# DriverV2_0.net
KiCad netlist of a schematic drawn in Altium Designer
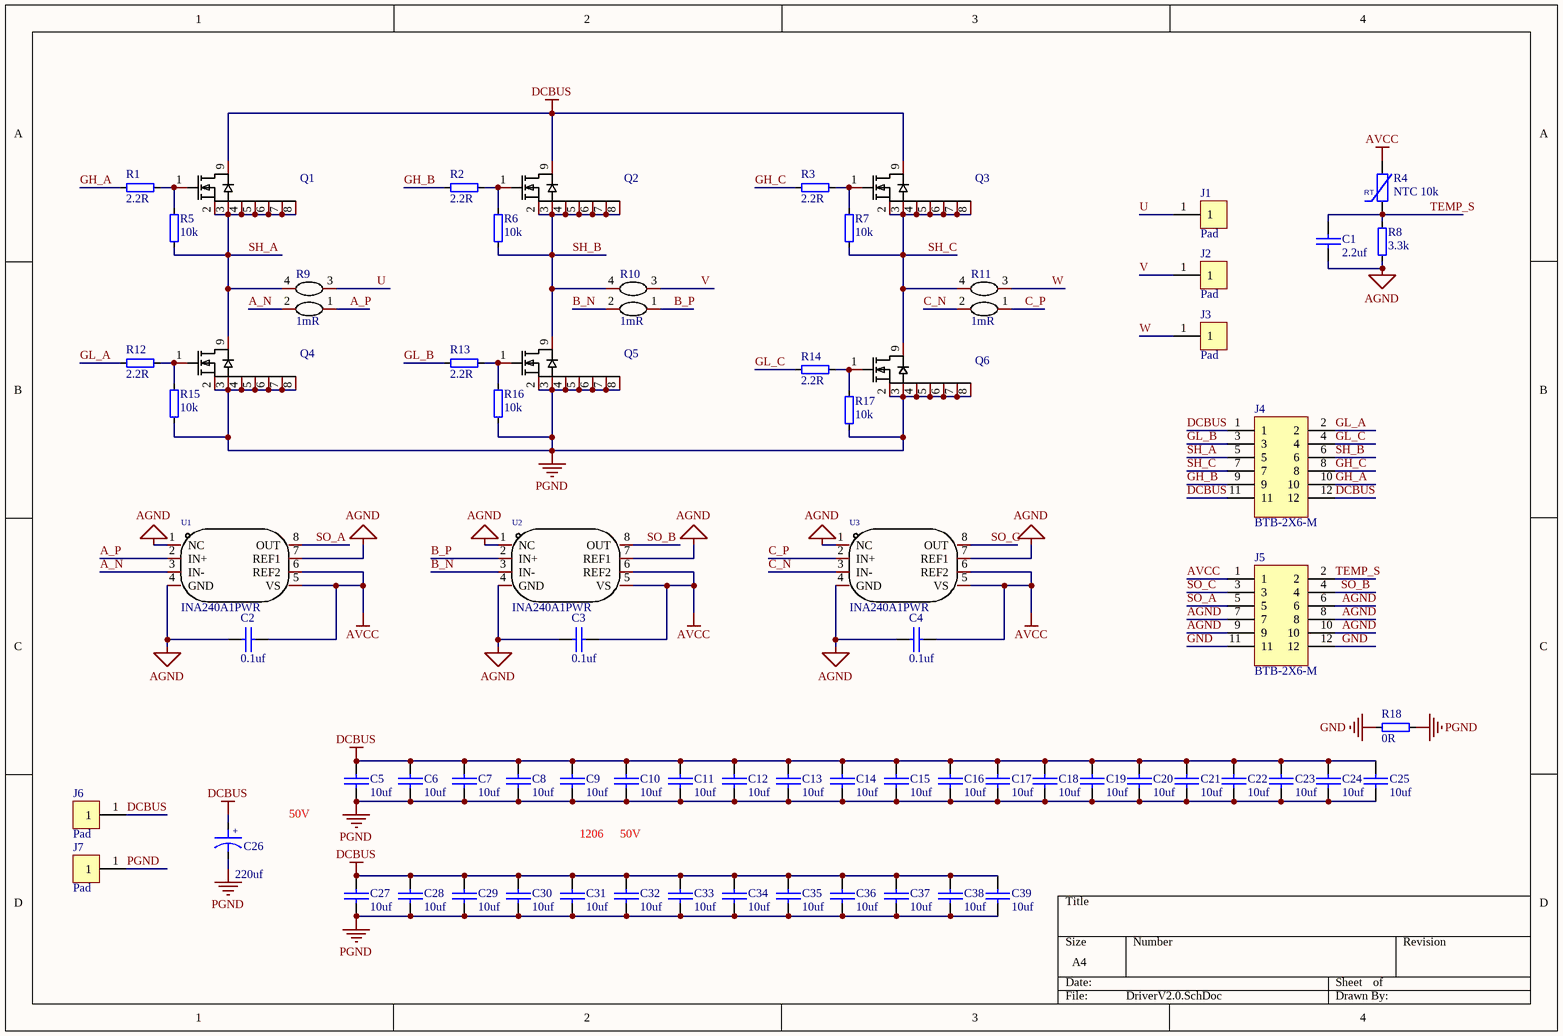
[diagram p0: DriverV2.0.SchDoc]

(export (version "E")
  (design (tool "Eeschema 10.0.6"))
  (components
    (comp (ref "C1")
      (value "2.2uf")
      (footprint "0603C")
      (description "贴片电容")
      (libsource (lib "Driver") (part "CAP"))
    )
    (comp (ref "C2")
      (value "0.1uf")
      (footprint "0603C")
      (description "贴片电容")
      (libsource (lib "Driver") (part "CAP"))
    )
    (comp (ref "C3")
      (value "0.1uf")
      (footprint "0603C")
      (description "贴片电容")
      (libsource (lib "Driver") (part "CAP"))
    )
    (comp (ref "C4")
      (value "0.1uf")
      (footprint "0603C")
      (description "贴片电容")
      (libsource (lib "Driver") (part "CAP"))
    )
    (comp (ref "C5")
      (value "10uf")
      (footprint "1206C")
      (description "贴片电容")
      (libsource (lib "Driver") (part "CAP"))
    )
    (comp (ref "C6")
      (value "10uf")
      (footprint "1206C")
      (description "贴片电容")
      (libsource (lib "Driver") (part "CAP"))
    )
    (comp (ref "C7")
      (value "10uf")
      (footprint "1206C")
      (description "贴片电容")
      (libsource (lib "Driver") (part "CAP"))
    )
    (comp (ref "C8")
      (value "10uf")
      (footprint "1206C")
      (description "贴片电容")
      (libsource (lib "Driver") (part "CAP"))
    )
    (comp (ref "C9")
      (value "10uf")
      (footprint "1206C")
      (description "贴片电容")
      (libsource (lib "Driver") (part "CAP"))
    )
    (comp (ref "C10")
      (value "10uf")
      (footprint "1206C")
      (description "贴片电容")
      (libsource (lib "Driver") (part "CAP"))
    )
    (comp (ref "C11")
      (value "10uf")
      (footprint "1206C")
      (description "贴片电容")
      (libsource (lib "Driver") (part "CAP"))
    )
    (comp (ref "C12")
      (value "10uf")
      (footprint "1206C")
      (description "贴片电容")
      (libsource (lib "Driver") (part "CAP"))
    )
    (comp (ref "C13")
      (value "10uf")
      (footprint "1206C")
      (description "贴片电容")
      (libsource (lib "Driver") (part "CAP"))
    )
    (comp (ref "C14")
      (value "10uf")
      (footprint "1206C")
      (description "贴片电容")
      (libsource (lib "Driver") (part "CAP"))
    )
    (comp (ref "C15")
      (value "10uf")
      (footprint "1206C")
      (description "贴片电容")
      (libsource (lib "Driver") (part "CAP"))
    )
    (comp (ref "C16")
      (value "10uf")
      (footprint "1206C")
      (description "贴片电容")
      (libsource (lib "Driver") (part "CAP"))
    )
    (comp (ref "C17")
      (value "10uf")
      (footprint "1206C")
      (description "贴片电容")
      (libsource (lib "Driver") (part "CAP"))
    )
    (comp (ref "C18")
      (value "10uf")
      (footprint "1206C")
      (description "贴片电容")
      (libsource (lib "Driver") (part "CAP"))
    )
    (comp (ref "C19")
      (value "10uf")
      (footprint "1206C")
      (description "贴片电容")
      (libsource (lib "Driver") (part "CAP"))
    )
    (comp (ref "C20")
      (value "10uf")
      (footprint "1206C")
      (description "贴片电容")
      (libsource (lib "Driver") (part "CAP"))
    )
    (comp (ref "C21")
      (value "10uf")
      (footprint "1206C")
      (description "贴片电容")
      (libsource (lib "Driver") (part "CAP"))
    )
    (comp (ref "C22")
      (value "10uf")
      (footprint "1206C")
      (description "贴片电容")
      (libsource (lib "Driver") (part "CAP"))
    )
    (comp (ref "C23")
      (value "10uf")
      (footprint "1206C")
      (description "贴片电容")
      (libsource (lib "Driver") (part "CAP"))
    )
    (comp (ref "C24")
      (value "10uf")
      (footprint "1206C")
      (description "贴片电容")
      (libsource (lib "Driver") (part "CAP"))
    )
    (comp (ref "C25")
      (value "10uf")
      (footprint "1206C")
      (description "贴片电容")
      (libsource (lib "Driver") (part "CAP"))
    )
    (comp (ref "C26")
      (value "220uf")
      (footprint "ELECTRO10-5-N")
      (description "极性电容")
      (libsource (lib "Driver") (part "CAP+"))
    )
    (comp (ref "C27")
      (value "10uf")
      (footprint "1206C")
      (description "贴片电容")
      (libsource (lib "Driver") (part "CAP"))
    )
    (comp (ref "C28")
      (value "10uf")
      (footprint "1206C")
      (description "贴片电容")
      (libsource (lib "Driver") (part "CAP"))
    )
    (comp (ref "C29")
      (value "10uf")
      (footprint "1206C")
      (description "贴片电容")
      (libsource (lib "Driver") (part "CAP"))
    )
    (comp (ref "C30")
      (value "10uf")
      (footprint "1206C")
      (description "贴片电容")
      (libsource (lib "Driver") (part "CAP"))
    )
    (comp (ref "C31")
      (value "10uf")
      (footprint "1206C")
      (description "贴片电容")
      (libsource (lib "Driver") (part "CAP"))
    )
    (comp (ref "C32")
      (value "10uf")
      (footprint "1206C")
      (description "贴片电容")
      (libsource (lib "Driver") (part "CAP"))
    )
    (comp (ref "C33")
      (value "10uf")
      (footprint "1206C")
      (description "贴片电容")
      (libsource (lib "Driver") (part "CAP"))
    )
    (comp (ref "C34")
      (value "10uf")
      (footprint "1206C")
      (description "贴片电容")
      (libsource (lib "Driver") (part "CAP"))
    )
    (comp (ref "C35")
      (value "10uf")
      (footprint "1206C")
      (description "贴片电容")
      (libsource (lib "Driver") (part "CAP"))
    )
    (comp (ref "C36")
      (value "10uf")
      (footprint "1206C")
      (description "贴片电容")
      (libsource (lib "Driver") (part "CAP"))
    )
    (comp (ref "C37")
      (value "10uf")
      (footprint "1206C")
      (description "贴片电容")
      (libsource (lib "Driver") (part "CAP"))
    )
    (comp (ref "C38")
      (value "10uf")
      (footprint "1206C")
      (description "贴片电容")
      (libsource (lib "Driver") (part "CAP"))
    )
    (comp (ref "C39")
      (value "10uf")
      (footprint "1206C")
      (description "贴片电容")
      (libsource (lib "Driver") (part "CAP"))
    )
    (comp (ref "J1")
      (value "Pad")
      (footprint "PAD")
      (description "焊盘")
      (libsource (lib "Driver") (part "Pad"))
    )
    (comp (ref "J2")
      (value "Pad")
      (footprint "PAD")
      (description "焊盘")
      (libsource (lib "Driver") (part "Pad"))
    )
    (comp (ref "J3")
      (value "Pad")
      (footprint "PAD")
      (description "焊盘")
      (libsource (lib "Driver") (part "Pad"))
    )
    (comp (ref "J4")
      (value "BTB-2X6-M")
      (footprint "BTB-M-0.8mm-2x6P")
      (description "0.8间距2x6P公座")
      (libsource (lib "Driver") (part "BTB-2X6-M"))
    )
    (comp (ref "J5")
      (value "BTB-2X6-M")
      (footprint "BTB-M-0.8mm-2x6P")
      (description "0.8间距2x6P公座")
      (libsource (lib "Driver") (part "BTB-2X6-M"))
    )
    (comp (ref "J6") (value "Pad") (footprint "PAD") (description "焊盘") (libsource (lib "") (part "Pad_1")))
    (comp (ref "J7") (value "Pad") (footprint "PAD") (description "焊盘") (libsource (lib "") (part "Pad_1")))
    (comp (ref "Q1")
      (value "HYG006N04LS1TA")
      (footprint "TOLL")
      (description "N沟道增强型MOS 40V-600A")
      (fields (field (name "MANUFACTURER") "HUAYI(华羿微)"))
      (libsource (lib "Driver") (part "HYG006N04LS1TA"))
    )
    (comp (ref "Q2")
      (value "HYG006N04LS1TA")
      (footprint "TOLL")
      (description "N沟道增强型MOS 40V-600A")
      (fields (field (name "MANUFACTURER") "HUAYI(华羿微)"))
      (libsource (lib "Driver") (part "HYG006N04LS1TA"))
    )
    (comp (ref "Q3")
      (value "HYG006N04LS1TA")
      (footprint "TOLL")
      (description "N沟道增强型MOS 40V-600A")
      (fields (field (name "MANUFACTURER") "HUAYI(华羿微)"))
      (libsource (lib "Driver") (part "HYG006N04LS1TA"))
    )
    (comp (ref "Q4")
      (value "HYG006N04LS1TA")
      (footprint "TOLL")
      (description "N沟道增强型MOS 40V-600A")
      (fields (field (name "MANUFACTURER") "HUAYI(华羿微)"))
      (libsource (lib "Driver") (part "HYG006N04LS1TA"))
    )
    (comp (ref "Q5")
      (value "HYG006N04LS1TA")
      (footprint "TOLL")
      (description "N沟道增强型MOS 40V-600A")
      (fields (field (name "MANUFACTURER") "HUAYI(华羿微)"))
      (libsource (lib "Driver") (part "HYG006N04LS1TA"))
    )
    (comp (ref "Q6")
      (value "HYG006N04LS1TA")
      (footprint "TOLL")
      (description "N沟道增强型MOS 40V-600A")
      (fields (field (name "MANUFACTURER") "HUAYI(华羿微)"))
      (libsource (lib "Driver") (part "HYG006N04LS1TA"))
    )
    (comp (ref "R1")
      (value "2.2R")
      (footprint "0603R")
      (description "贴片电阻")
      (libsource (lib "Driver") (part "RES"))
    )
    (comp (ref "R2")
      (value "2.2R")
      (footprint "0603R")
      (description "贴片电阻")
      (libsource (lib "Driver") (part "RES"))
    )
    (comp (ref "R3")
      (value "2.2R")
      (footprint "0603R")
      (description "贴片电阻")
      (libsource (lib "Driver") (part "RES"))
    )
    (comp (ref "R4")
      (value "NTC 10k")
      (footprint "0805R")
      (description "热敏电阻")
      (libsource (lib "Driver") (part "RT"))
    )
    (comp (ref "R5")
      (value "10k")
      (footprint "0603R")
      (description "贴片电阻")
      (libsource (lib "Driver") (part "RES"))
    )
    (comp (ref "R6")
      (value "10k")
      (footprint "0603R")
      (description "贴片电阻")
      (libsource (lib "Driver") (part "RES"))
    )
    (comp (ref "R7")
      (value "10k")
      (footprint "0603R")
      (description "贴片电阻")
      (libsource (lib "Driver") (part "RES"))
    )
    (comp (ref "R8")
      (value "3.3k")
      (footprint "0603R")
      (description "贴片电阻")
      (libsource (lib "Driver") (part "RES"))
    )
    (comp (ref "R9")
      (value "1mR")
      (footprint "3637R")
      (description "四脚采样电阻")
      (fields
        (field (name "MANUFACTURER") "Milliohm(毫欧)")
        (field (name "MANUFACTURER PART") "HoLR3637-5-R010-F")
      )
      (libsource (lib "Driver") (part "HoLR3637"))
    )
    (comp (ref "R10")
      (value "1mR")
      (footprint "3637R")
      (description "四脚采样电阻")
      (fields
        (field (name "MANUFACTURER") "Milliohm(毫欧)")
        (field (name "MANUFACTURER PART") "HoLR3637-5-R010-F")
      )
      (libsource (lib "Driver") (part "HoLR3637"))
    )
    (comp (ref "R11")
      (value "1mR")
      (footprint "3637R")
      (description "四脚采样电阻")
      (fields
        (field (name "MANUFACTURER") "Milliohm(毫欧)")
        (field (name "MANUFACTURER PART") "HoLR3637-5-R010-F")
      )
      (libsource (lib "Driver") (part "HoLR3637"))
    )
    (comp (ref "R12")
      (value "2.2R")
      (footprint "0603R")
      (description "贴片电阻")
      (libsource (lib "Driver") (part "RES"))
    )
    (comp (ref "R13")
      (value "2.2R")
      (footprint "0603R")
      (description "贴片电阻")
      (libsource (lib "Driver") (part "RES"))
    )
    (comp (ref "R14")
      (value "2.2R")
      (footprint "0603R")
      (description "贴片电阻")
      (libsource (lib "Driver") (part "RES"))
    )
    (comp (ref "R15")
      (value "10k")
      (footprint "0603R")
      (description "贴片电阻")
      (libsource (lib "Driver") (part "RES"))
    )
    (comp (ref "R16")
      (value "10k")
      (footprint "0603R")
      (description "贴片电阻")
      (libsource (lib "Driver") (part "RES"))
    )
    (comp (ref "R17")
      (value "10k")
      (footprint "0603R")
      (description "贴片电阻")
      (libsource (lib "Driver") (part "RES"))
    )
    (comp (ref "R18")
      (value "0R")
      (footprint "0603R")
      (description "贴片电阻")
      (libsource (lib "Driver") (part "RES"))
    )
    (comp (ref "U1")
      (value "INA240A1PWR")
      (footprint "TSSOP-8")
      (fields (field (name "MANUFACTURER") "TI(德州仪器)") (field (name "NAME") "INA240A1PWR"))
      (libsource (lib "Driver") (part "INA240A1PWR"))
    )
    (comp (ref "U2")
      (value "INA240A1PWR")
      (footprint "TSSOP-8")
      (fields (field (name "MANUFACTURER") "TI(德州仪器)") (field (name "NAME") "INA240A1PWR"))
      (libsource (lib "Driver") (part "INA240A1PWR"))
    )
    (comp (ref "U3")
      (value "INA240A1PWR")
      (footprint "TSSOP-8")
      (fields (field (name "MANUFACTURER") "TI(德州仪器)") (field (name "NAME") "INA240A1PWR"))
      (libsource (lib "Driver") (part "INA240A1PWR"))
    )
  )
  (nets
    (net (code "1") (name "/A_N") (class "Default")
      (node (ref "R9") (pin "2") (pinfunction "2_2") (pintype "passive"))
      (node (ref "U1") (pin "3") (pinfunction "IN-_3") (pintype "passive"))
    )
    (net (code "2") (name "/A_P") (class "Default")
      (node (ref "R9") (pin "1") (pinfunction "1_1") (pintype "passive"))
      (node (ref "U1") (pin "2") (pinfunction "IN+_2") (pintype "passive"))
    )
    (net (code "3") (name "/B_N") (class "Default")
      (node (ref "R10") (pin "2") (pinfunction "2_2") (pintype "passive"))
      (node (ref "U2") (pin "3") (pinfunction "IN-_3") (pintype "passive"))
    )
    (net (code "4") (name "/B_P") (class "Default")
      (node (ref "R10") (pin "1") (pinfunction "1_1") (pintype "passive"))
      (node (ref "U2") (pin "2") (pinfunction "IN+_2") (pintype "passive"))
    )
    (net (code "5") (name "/C_N") (class "Default")
      (node (ref "R11") (pin "2") (pinfunction "2_2") (pintype "passive"))
      (node (ref "U3") (pin "3") (pinfunction "IN-_3") (pintype "passive"))
    )
    (net (code "6") (name "/C_P") (class "Default")
      (node (ref "R11") (pin "1") (pinfunction "1_1") (pintype "passive"))
      (node (ref "U3") (pin "2") (pinfunction "IN+_2") (pintype "passive"))
    )
    (net (code "7") (name "/GH_A") (class "Default")
      (node (ref "J4") (pin "10") (pinfunction "10_10") (pintype "passive"))
      (node (ref "R1") (pin "1") (pinfunction "1_1") (pintype "passive"))
    )
    (net (code "8") (name "/GH_B") (class "Default")
      (node (ref "J4") (pin "9") (pinfunction "9_9") (pintype "passive"))
      (node (ref "R2") (pin "1") (pinfunction "1_1") (pintype "passive"))
    )
    (net (code "9") (name "/GH_C") (class "Default")
      (node (ref "J4") (pin "8") (pinfunction "8_8") (pintype "passive"))
      (node (ref "R3") (pin "1") (pinfunction "1_1") (pintype "passive"))
    )
    (net (code "10") (name "/GL_A") (class "Default")
      (node (ref "J4") (pin "2") (pinfunction "2_2") (pintype "passive"))
      (node (ref "R12") (pin "1") (pinfunction "1_1") (pintype "passive"))
    )
    (net (code "11") (name "/GL_B") (class "Default")
      (node (ref "J4") (pin "3") (pinfunction "3_3") (pintype "passive"))
      (node (ref "R13") (pin "1") (pinfunction "1_1") (pintype "passive"))
    )
    (net (code "12") (name "/GL_C") (class "Default")
      (node (ref "J4") (pin "4") (pinfunction "4_4") (pintype "passive"))
      (node (ref "R14") (pin "1") (pinfunction "1_1") (pintype "passive"))
    )
    (net (code "13") (name "/SH_A") (class "Default")
      (node (ref "J4") (pin "5") (pinfunction "5_5") (pintype "passive"))
      (node (ref "Q1") (pin "2") (pinfunction "S_2") (pintype "passive"))
      (node (ref "Q1") (pin "3") (pinfunction "S_3") (pintype "passive"))
      (node (ref "Q1") (pin "4") (pinfunction "S_4") (pintype "passive"))
      (node (ref "Q1") (pin "5") (pinfunction "S_5") (pintype "passive"))
      (node (ref "Q1") (pin "6") (pinfunction "S_6") (pintype "passive"))
      (node (ref "Q1") (pin "7") (pinfunction "S_7") (pintype "passive"))
      (node (ref "Q1") (pin "8") (pinfunction "S_8") (pintype "passive"))
      (node (ref "Q4") (pin "9") (pinfunction "D_9") (pintype "passive"))
      (node (ref "R5") (pin "1") (pinfunction "1_1") (pintype "passive"))
      (node (ref "R9") (pin "4") (pinfunction "4_4") (pintype "passive"))
    )
    (net (code "14") (name "/SH_B") (class "Default")
      (node (ref "J4") (pin "6") (pinfunction "6_6") (pintype "passive"))
      (node (ref "Q2") (pin "2") (pinfunction "S_2") (pintype "passive"))
      (node (ref "Q2") (pin "3") (pinfunction "S_3") (pintype "passive"))
      (node (ref "Q2") (pin "4") (pinfunction "S_4") (pintype "passive"))
      (node (ref "Q2") (pin "5") (pinfunction "S_5") (pintype "passive"))
      (node (ref "Q2") (pin "6") (pinfunction "S_6") (pintype "passive"))
      (node (ref "Q2") (pin "7") (pinfunction "S_7") (pintype "passive"))
      (node (ref "Q2") (pin "8") (pinfunction "S_8") (pintype "passive"))
      (node (ref "Q5") (pin "9") (pinfunction "D_9") (pintype "passive"))
      (node (ref "R10") (pin "4") (pinfunction "4_4") (pintype "passive"))
      (node (ref "R6") (pin "1") (pinfunction "1_1") (pintype "passive"))
    )
    (net (code "15") (name "/SH_C") (class "Default")
      (node (ref "J4") (pin "7") (pinfunction "7_7") (pintype "passive"))
      (node (ref "Q3") (pin "2") (pinfunction "S_2") (pintype "passive"))
      (node (ref "Q3") (pin "3") (pinfunction "S_3") (pintype "passive"))
      (node (ref "Q3") (pin "4") (pinfunction "S_4") (pintype "passive"))
      (node (ref "Q3") (pin "5") (pinfunction "S_5") (pintype "passive"))
      (node (ref "Q3") (pin "6") (pinfunction "S_6") (pintype "passive"))
      (node (ref "Q3") (pin "7") (pinfunction "S_7") (pintype "passive"))
      (node (ref "Q3") (pin "8") (pinfunction "S_8") (pintype "passive"))
      (node (ref "Q6") (pin "9") (pinfunction "D_9") (pintype "passive"))
      (node (ref "R11") (pin "4") (pinfunction "4_4") (pintype "passive"))
      (node (ref "R7") (pin "1") (pinfunction "1_1") (pintype "passive"))
    )
    (net (code "16") (name "/SO_A") (class "Default")
      (node (ref "J5") (pin "5") (pinfunction "5_5") (pintype "passive"))
      (node (ref "U1") (pin "8") (pinfunction "OUT_8") (pintype "passive"))
    )
    (net (code "17") (name "/SO_B") (class "Default")
      (node (ref "J5") (pin "4") (pinfunction "4_4") (pintype "passive"))
      (node (ref "U2") (pin "8") (pinfunction "OUT_8") (pintype "passive"))
    )
    (net (code "18") (name "/SO_C") (class "Default")
      (node (ref "J5") (pin "3") (pinfunction "3_3") (pintype "passive"))
      (node (ref "U3") (pin "8") (pinfunction "OUT_8") (pintype "passive"))
    )
    (net (code "19") (name "/TEMP_S") (class "Default")
      (node (ref "C1") (pin "1") (pinfunction "1_1") (pintype "passive"))
      (node (ref "J5") (pin "2") (pinfunction "2_2") (pintype "passive"))
      (node (ref "R4") (pin "1") (pinfunction "1_1") (pintype "passive"))
      (node (ref "R8") (pin "2") (pinfunction "2_2") (pintype "passive"))
    )
    (net (code "20") (name "/U") (class "Default")
      (node (ref "J1") (pin "1") (pinfunction "1_1") (pintype "passive"))
      (node (ref "R9") (pin "3") (pinfunction "3_3") (pintype "passive"))
    )
    (net (code "21") (name "/V") (class "Default")
      (node (ref "J2") (pin "1") (pinfunction "1_1") (pintype "passive"))
      (node (ref "R10") (pin "3") (pinfunction "3_3") (pintype "passive"))
    )
    (net (code "22") (name "/W") (class "Default")
      (node (ref "J3") (pin "1") (pinfunction "1_1") (pintype "passive"))
      (node (ref "R11") (pin "3") (pinfunction "3_3") (pintype "passive"))
    )
    (net (code "23") (name "AGND") (class "Default")
      (node (ref "C1") (pin "2") (pinfunction "2_2") (pintype "passive"))
      (node (ref "C2") (pin "1") (pinfunction "1_1") (pintype "passive"))
      (node (ref "C3") (pin "1") (pinfunction "1_1") (pintype "passive"))
      (node (ref "C4") (pin "1") (pinfunction "1_1") (pintype "passive"))
      (node (ref "J5") (pin "10") (pinfunction "10_10") (pintype "passive"))
      (node (ref "J5") (pin "6") (pinfunction "6_6") (pintype "passive"))
      (node (ref "J5") (pin "7") (pinfunction "7_7") (pintype "passive"))
      (node (ref "J5") (pin "8") (pinfunction "8_8") (pintype "passive"))
      (node (ref "J5") (pin "9") (pinfunction "9_9") (pintype "passive"))
      (node (ref "R8") (pin "1") (pinfunction "1_1") (pintype "passive"))
      (node (ref "U1") (pin "1") (pinfunction "NC_1") (pintype "passive"))
      (node (ref "U1") (pin "4") (pinfunction "GND_4") (pintype "passive"))
      (node (ref "U1") (pin "7") (pinfunction "REF1_7") (pintype "passive"))
      (node (ref "U2") (pin "1") (pinfunction "NC_1") (pintype "passive"))
      (node (ref "U2") (pin "4") (pinfunction "GND_4") (pintype "passive"))
      (node (ref "U2") (pin "7") (pinfunction "REF1_7") (pintype "passive"))
      (node (ref "U3") (pin "1") (pinfunction "NC_1") (pintype "passive"))
      (node (ref "U3") (pin "4") (pinfunction "GND_4") (pintype "passive"))
      (node (ref "U3") (pin "7") (pinfunction "REF1_7") (pintype "passive"))
    )
    (net (code "24") (name "AVCC") (class "Default")
      (node (ref "C2") (pin "2") (pinfunction "2_2") (pintype "passive"))
      (node (ref "C3") (pin "2") (pinfunction "2_2") (pintype "passive"))
      (node (ref "C4") (pin "2") (pinfunction "2_2") (pintype "passive"))
      (node (ref "J5") (pin "1") (pinfunction "1_1") (pintype "passive"))
      (node (ref "R4") (pin "2") (pinfunction "2_2") (pintype "passive"))
      (node (ref "U1") (pin "5") (pinfunction "VS_5") (pintype "passive"))
      (node (ref "U1") (pin "6") (pinfunction "REF2_6") (pintype "passive"))
      (node (ref "U2") (pin "5") (pinfunction "VS_5") (pintype "passive"))
      (node (ref "U2") (pin "6") (pinfunction "REF2_6") (pintype "passive"))
      (node (ref "U3") (pin "5") (pinfunction "VS_5") (pintype "passive"))
      (node (ref "U3") (pin "6") (pinfunction "REF2_6") (pintype "passive"))
    )
    (net (code "25") (name "DCBUS") (class "Default")
      (node (ref "C10") (pin "1") (pinfunction "1_1") (pintype "passive"))
      (node (ref "C11") (pin "1") (pinfunction "1_1") (pintype "passive"))
      (node (ref "C12") (pin "1") (pinfunction "1_1") (pintype "passive"))
      (node (ref "C13") (pin "1") (pinfunction "1_1") (pintype "passive"))
      (node (ref "C14") (pin "1") (pinfunction "1_1") (pintype "passive"))
      (node (ref "C15") (pin "1") (pinfunction "1_1") (pintype "passive"))
      (node (ref "C16") (pin "1") (pinfunction "1_1") (pintype "passive"))
      (node (ref "C17") (pin "1") (pinfunction "1_1") (pintype "passive"))
      (node (ref "C18") (pin "1") (pinfunction "1_1") (pintype "passive"))
      (node (ref "C19") (pin "1") (pinfunction "1_1") (pintype "passive"))
      (node (ref "C20") (pin "1") (pinfunction "1_1") (pintype "passive"))
      (node (ref "C21") (pin "1") (pinfunction "1_1") (pintype "passive"))
      (node (ref "C22") (pin "1") (pinfunction "1_1") (pintype "passive"))
      (node (ref "C23") (pin "1") (pinfunction "1_1") (pintype "passive"))
      (node (ref "C24") (pin "1") (pinfunction "1_1") (pintype "passive"))
      (node (ref "C25") (pin "1") (pinfunction "1_1") (pintype "passive"))
      (node (ref "C26") (pin "1") (pinfunction "1_1") (pintype "passive"))
      (node (ref "C27") (pin "1") (pinfunction "1_1") (pintype "passive"))
      (node (ref "C28") (pin "1") (pinfunction "1_1") (pintype "passive"))
      (node (ref "C29") (pin "1") (pinfunction "1_1") (pintype "passive"))
      (node (ref "C30") (pin "1") (pinfunction "1_1") (pintype "passive"))
      (node (ref "C31") (pin "1") (pinfunction "1_1") (pintype "passive"))
      (node (ref "C32") (pin "1") (pinfunction "1_1") (pintype "passive"))
      (node (ref "C33") (pin "1") (pinfunction "1_1") (pintype "passive"))
      (node (ref "C34") (pin "1") (pinfunction "1_1") (pintype "passive"))
      (node (ref "C35") (pin "1") (pinfunction "1_1") (pintype "passive"))
      (node (ref "C36") (pin "1") (pinfunction "1_1") (pintype "passive"))
      (node (ref "C37") (pin "1") (pinfunction "1_1") (pintype "passive"))
      (node (ref "C38") (pin "1") (pinfunction "1_1") (pintype "passive"))
      (node (ref "C39") (pin "1") (pinfunction "1_1") (pintype "passive"))
      (node (ref "C5") (pin "1") (pinfunction "1_1") (pintype "passive"))
      (node (ref "C6") (pin "1") (pinfunction "1_1") (pintype "passive"))
      (node (ref "C7") (pin "1") (pinfunction "1_1") (pintype "passive"))
      (node (ref "C8") (pin "1") (pinfunction "1_1") (pintype "passive"))
      (node (ref "C9") (pin "1") (pinfunction "1_1") (pintype "passive"))
      (node (ref "J4") (pin "1") (pinfunction "1_1") (pintype "passive"))
      (node (ref "J4") (pin "11") (pinfunction "11_11") (pintype "passive"))
      (node (ref "J4") (pin "12") (pinfunction "12_12") (pintype "passive"))
      (node (ref "J6") (pin "1") (pinfunction "1_1") (pintype "passive"))
      (node (ref "Q1") (pin "9") (pinfunction "D_9") (pintype "passive"))
      (node (ref "Q2") (pin "9") (pinfunction "D_9") (pintype "passive"))
      (node (ref "Q3") (pin "9") (pinfunction "D_9") (pintype "passive"))
    )
    (net (code "26") (name "GND") (class "Default")
      (node (ref "J5") (pin "11") (pinfunction "11_11") (pintype "passive"))
      (node (ref "J5") (pin "12") (pinfunction "12_12") (pintype "passive"))
      (node (ref "R18") (pin "2") (pinfunction "2_2") (pintype "passive"))
    )
    (net (code "27") (name "Net-(Q1-G)") (class "Default")
      (node (ref "Q1") (pin "1") (pinfunction "G_1") (pintype "passive"))
      (node (ref "R1") (pin "2") (pinfunction "2_2") (pintype "passive"))
      (node (ref "R5") (pin "2") (pinfunction "2_2") (pintype "passive"))
    )
    (net (code "28") (name "Net-(Q2-G)") (class "Default")
      (node (ref "Q2") (pin "1") (pinfunction "G_1") (pintype "passive"))
      (node (ref "R2") (pin "2") (pinfunction "2_2") (pintype "passive"))
      (node (ref "R6") (pin "2") (pinfunction "2_2") (pintype "passive"))
    )
    (net (code "29") (name "Net-(Q3-G)") (class "Default")
      (node (ref "Q3") (pin "1") (pinfunction "G_1") (pintype "passive"))
      (node (ref "R3") (pin "2") (pinfunction "2_2") (pintype "passive"))
      (node (ref "R7") (pin "2") (pinfunction "2_2") (pintype "passive"))
    )
    (net (code "30") (name "Net-(Q4-G)") (class "Default")
      (node (ref "Q4") (pin "1") (pinfunction "G_1") (pintype "passive"))
      (node (ref "R12") (pin "2") (pinfunction "2_2") (pintype "passive"))
      (node (ref "R15") (pin "2") (pinfunction "2_2") (pintype "passive"))
    )
    (net (code "31") (name "Net-(Q5-G)") (class "Default")
      (node (ref "Q5") (pin "1") (pinfunction "G_1") (pintype "passive"))
      (node (ref "R13") (pin "2") (pinfunction "2_2") (pintype "passive"))
      (node (ref "R16") (pin "2") (pinfunction "2_2") (pintype "passive"))
    )
    (net (code "32") (name "Net-(Q6-G)") (class "Default")
      (node (ref "Q6") (pin "1") (pinfunction "G_1") (pintype "passive"))
      (node (ref "R14") (pin "2") (pinfunction "2_2") (pintype "passive"))
      (node (ref "R17") (pin "2") (pinfunction "2_2") (pintype "passive"))
    )
    (net (code "33") (name "PGND") (class "Default")
      (node (ref "C10") (pin "2") (pinfunction "2_2") (pintype "passive"))
      (node (ref "C11") (pin "2") (pinfunction "2_2") (pintype "passive"))
      (node (ref "C12") (pin "2") (pinfunction "2_2") (pintype "passive"))
      (node (ref "C13") (pin "2") (pinfunction "2_2") (pintype "passive"))
      (node (ref "C14") (pin "2") (pinfunction "2_2") (pintype "passive"))
      (node (ref "C15") (pin "2") (pinfunction "2_2") (pintype "passive"))
      (node (ref "C16") (pin "2") (pinfunction "2_2") (pintype "passive"))
      (node (ref "C17") (pin "2") (pinfunction "2_2") (pintype "passive"))
      (node (ref "C18") (pin "2") (pinfunction "2_2") (pintype "passive"))
      (node (ref "C19") (pin "2") (pinfunction "2_2") (pintype "passive"))
      (node (ref "C20") (pin "2") (pinfunction "2_2") (pintype "passive"))
      (node (ref "C21") (pin "2") (pinfunction "2_2") (pintype "passive"))
      (node (ref "C22") (pin "2") (pinfunction "2_2") (pintype "passive"))
      (node (ref "C23") (pin "2") (pinfunction "2_2") (pintype "passive"))
      (node (ref "C24") (pin "2") (pinfunction "2_2") (pintype "passive"))
      (node (ref "C25") (pin "2") (pinfunction "2_2") (pintype "passive"))
      (node (ref "C26") (pin "2") (pinfunction "2_2") (pintype "passive"))
      (node (ref "C27") (pin "2") (pinfunction "2_2") (pintype "passive"))
      (node (ref "C28") (pin "2") (pinfunction "2_2") (pintype "passive"))
      (node (ref "C29") (pin "2") (pinfunction "2_2") (pintype "passive"))
      (node (ref "C30") (pin "2") (pinfunction "2_2") (pintype "passive"))
      (node (ref "C31") (pin "2") (pinfunction "2_2") (pintype "passive"))
      (node (ref "C32") (pin "2") (pinfunction "2_2") (pintype "passive"))
      (node (ref "C33") (pin "2") (pinfunction "2_2") (pintype "passive"))
      (node (ref "C34") (pin "2") (pinfunction "2_2") (pintype "passive"))
      (node (ref "C35") (pin "2") (pinfunction "2_2") (pintype "passive"))
      (node (ref "C36") (pin "2") (pinfunction "2_2") (pintype "passive"))
      (node (ref "C37") (pin "2") (pinfunction "2_2") (pintype "passive"))
      (node (ref "C38") (pin "2") (pinfunction "2_2") (pintype "passive"))
      (node (ref "C39") (pin "2") (pinfunction "2_2") (pintype "passive"))
      (node (ref "C5") (pin "2") (pinfunction "2_2") (pintype "passive"))
      (node (ref "C6") (pin "2") (pinfunction "2_2") (pintype "passive"))
      (node (ref "C7") (pin "2") (pinfunction "2_2") (pintype "passive"))
      (node (ref "C8") (pin "2") (pinfunction "2_2") (pintype "passive"))
      (node (ref "C9") (pin "2") (pinfunction "2_2") (pintype "passive"))
      (node (ref "J7") (pin "1") (pinfunction "1_1") (pintype "passive"))
      (node (ref "Q4") (pin "2") (pinfunction "S_2") (pintype "passive"))
      (node (ref "Q4") (pin "3") (pinfunction "S_3") (pintype "passive"))
      (node (ref "Q4") (pin "4") (pinfunction "S_4") (pintype "passive"))
      (node (ref "Q4") (pin "5") (pinfunction "S_5") (pintype "passive"))
      (node (ref "Q4") (pin "6") (pinfunction "S_6") (pintype "passive"))
      (node (ref "Q4") (pin "7") (pinfunction "S_7") (pintype "passive"))
      (node (ref "Q4") (pin "8") (pinfunction "S_8") (pintype "passive"))
      (node (ref "Q5") (pin "2") (pinfunction "S_2") (pintype "passive"))
      (node (ref "Q5") (pin "3") (pinfunction "S_3") (pintype "passive"))
      (node (ref "Q5") (pin "4") (pinfunction "S_4") (pintype "passive"))
      (node (ref "Q5") (pin "5") (pinfunction "S_5") (pintype "passive"))
      (node (ref "Q5") (pin "6") (pinfunction "S_6") (pintype "passive"))
      (node (ref "Q5") (pin "7") (pinfunction "S_7") (pintype "passive"))
      (node (ref "Q5") (pin "8") (pinfunction "S_8") (pintype "passive"))
      (node (ref "Q6") (pin "2") (pinfunction "S_2") (pintype "passive"))
      (node (ref "Q6") (pin "3") (pinfunction "S_3") (pintype "passive"))
      (node (ref "Q6") (pin "4") (pinfunction "S_4") (pintype "passive"))
      (node (ref "Q6") (pin "5") (pinfunction "S_5") (pintype "passive"))
      (node (ref "Q6") (pin "6") (pinfunction "S_6") (pintype "passive"))
      (node (ref "Q6") (pin "7") (pinfunction "S_7") (pintype "passive"))
      (node (ref "Q6") (pin "8") (pinfunction "S_8") (pintype "passive"))
      (node (ref "R15") (pin "1") (pinfunction "1_1") (pintype "passive"))
      (node (ref "R16") (pin "1") (pinfunction "1_1") (pintype "passive"))
      (node (ref "R17") (pin "1") (pinfunction "1_1") (pintype "passive"))
      (node (ref "R18") (pin "1") (pinfunction "1_1") (pintype "passive"))
    )
  )
)
